# sensori_di_linea_soccer_2018.net
KiCad netlist of a schematic drawn in EAGLE
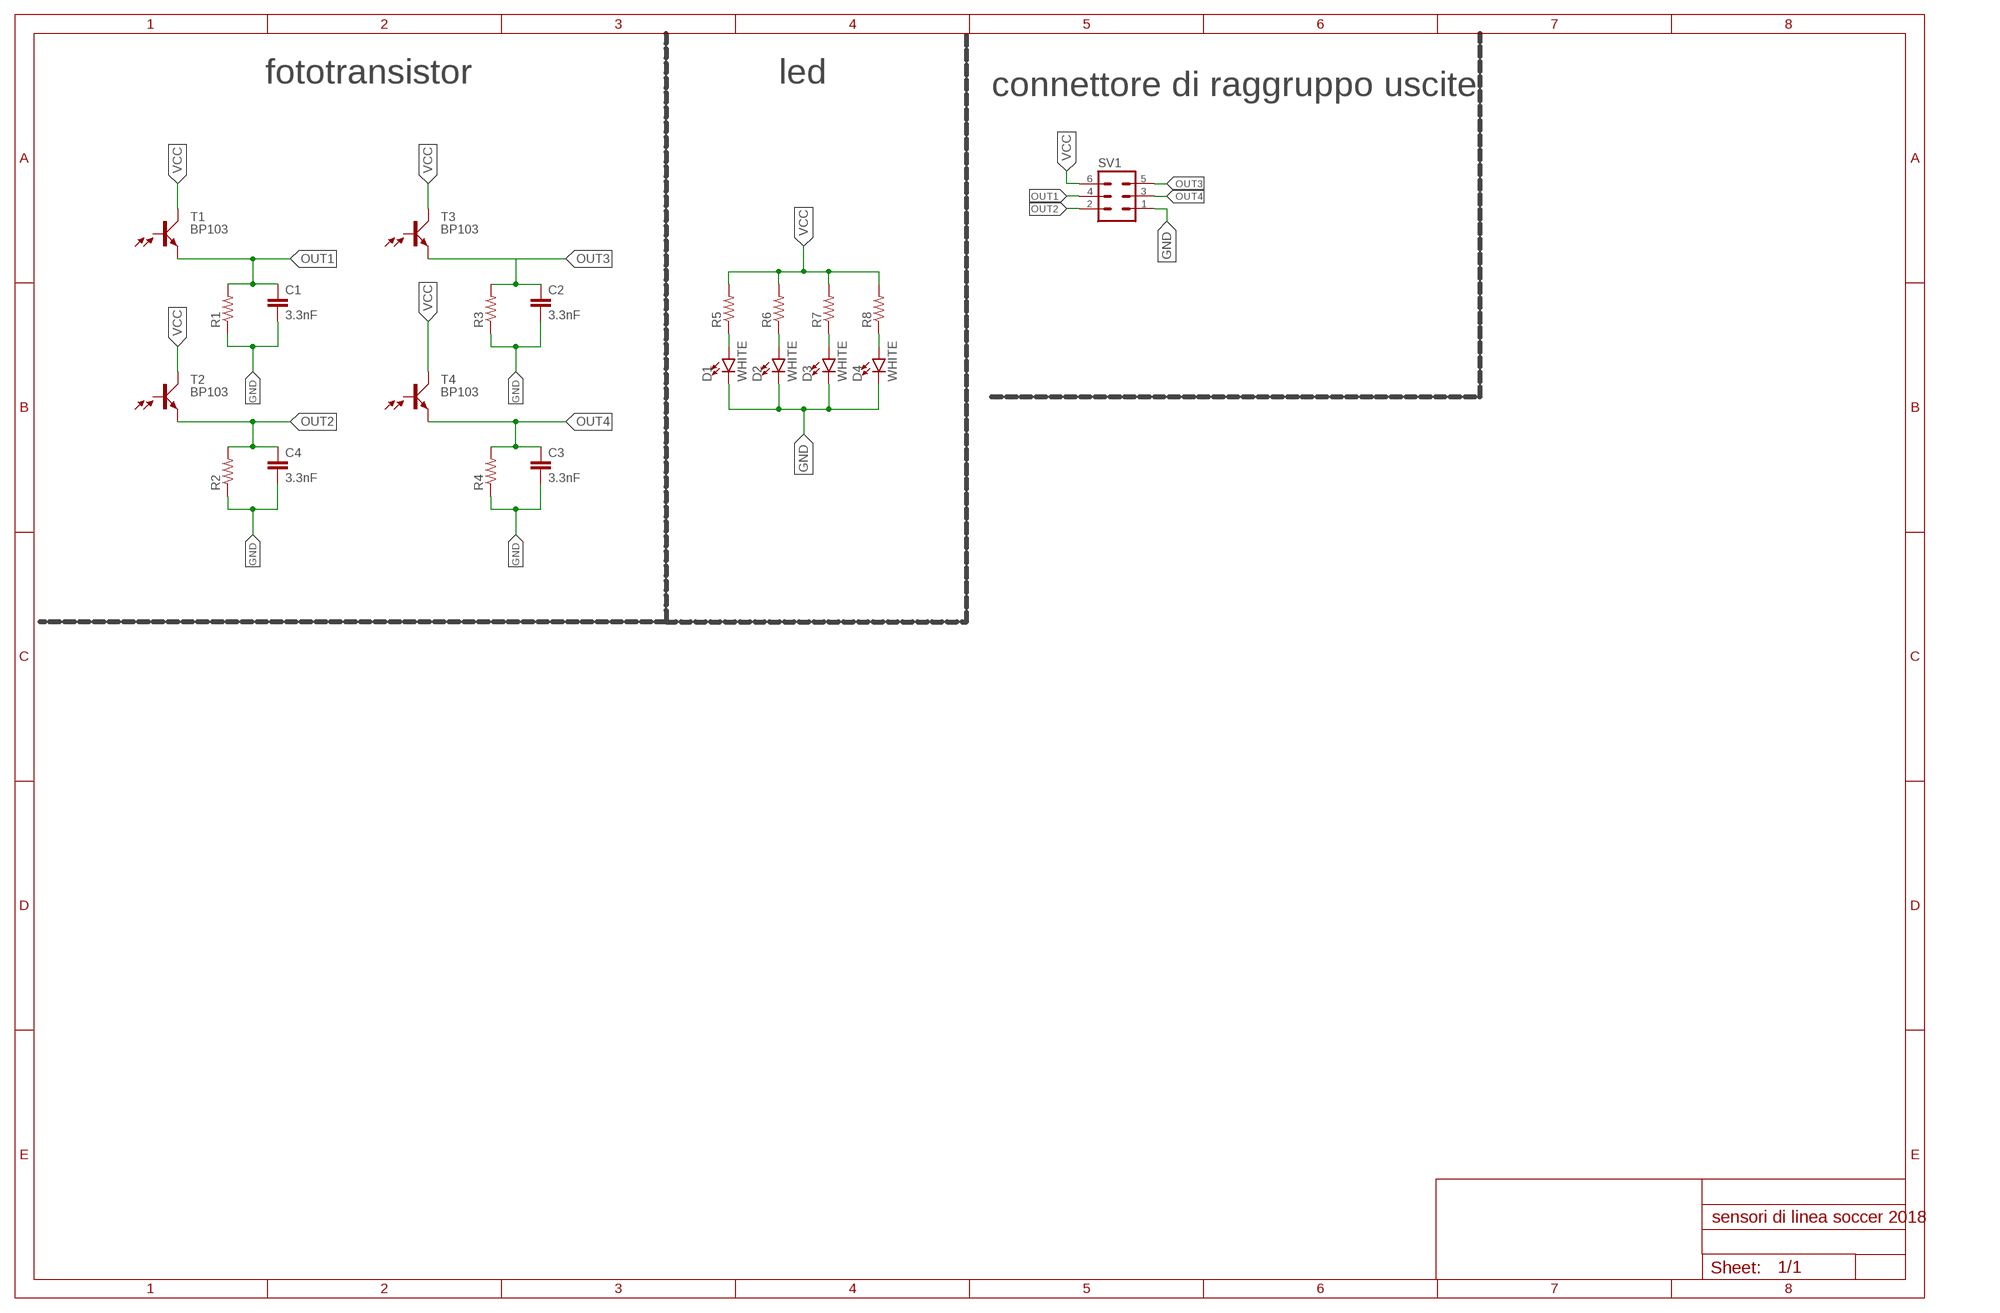
[diagram p0: schematic, sheet 1]

(export (version "E")
  (design (tool "Eeschema 10.0.6"))
  (components
    (comp (ref "C1")
      (value "3.3nF")
      (footprint "eagle-import:0603")
      (libsource (lib "eagle-import") (part "3.3NF-0603-100V-10%"))
    )
    (comp (ref "C2")
      (value "3.3nF")
      (footprint "eagle-import:0603")
      (libsource (lib "eagle-import") (part "3.3NF-0603-100V-10%"))
    )
    (comp (ref "C3")
      (value "3.3nF")
      (footprint "eagle-import:0603")
      (libsource (lib "eagle-import") (part "3.3NF-0603-100V-10%"))
    )
    (comp (ref "C4")
      (value "3.3nF")
      (footprint "eagle-import:0603")
      (libsource (lib "eagle-import") (part "3.3NF-0603-100V-10%"))
    )
    (comp (ref "D1")
      (value "WHITE")
      (footprint "eagle-import:LED-1206")
      (libsource (lib "eagle-import") (part "LED-WHITE1206"))
    )
    (comp (ref "D2")
      (value "WHITE")
      (footprint "eagle-import:LED-1206")
      (libsource (lib "eagle-import") (part "LED-WHITE1206"))
    )
    (comp (ref "D3")
      (value "WHITE")
      (footprint "eagle-import:LED-1206")
      (libsource (lib "eagle-import") (part "LED-WHITE1206"))
    )
    (comp (ref "D4")
      (value "WHITE")
      (footprint "eagle-import:LED-1206")
      (libsource (lib "eagle-import") (part "LED-WHITE1206"))
    )
    (comp (ref "R1")
      (value "R-US_0204/7")
      (footprint "eagle-import:0204_7")
      (libsource (lib "eagle-import") (part "resistor_348_R-US_0204/7"))
    )
    (comp (ref "R2")
      (value "R-US_0204/7")
      (footprint "eagle-import:0204_7")
      (libsource (lib "eagle-import") (part "resistor_348_R-US_0204/7"))
    )
    (comp (ref "R3")
      (value "R-US_0204/7")
      (footprint "eagle-import:0204_7")
      (libsource (lib "eagle-import") (part "resistor_348_R-US_0204/7"))
    )
    (comp (ref "R4")
      (value "R-US_0204/7")
      (footprint "eagle-import:0204_7")
      (libsource (lib "eagle-import") (part "resistor_348_R-US_0204/7"))
    )
    (comp (ref "R5")
      (value "R-US_0204/7")
      (footprint "eagle-import:0204_7")
      (libsource (lib "eagle-import") (part "R-US_0204/7"))
    )
    (comp (ref "R6")
      (value "R-US_0204/7")
      (footprint "eagle-import:0204_7")
      (libsource (lib "eagle-import") (part "R-US_0204/7"))
    )
    (comp (ref "R7")
      (value "R-US_0204/7")
      (footprint "eagle-import:0204_7")
      (libsource (lib "eagle-import") (part "R-US_0204/7"))
    )
    (comp (ref "R8")
      (value "R-US_0204/7")
      (footprint "eagle-import:0204_7")
      (libsource (lib "eagle-import") (part "R-US_0204/7"))
    )
    (comp (ref "SV1")
      (value "MA03-2")
      (footprint "eagle-import:MA03-2")
      (libsource (lib "eagle-import") (part "MA03-2"))
    )
    (comp (ref "T1")
      (value "BP103")
      (footprint "eagle-import:BP103")
      (libsource (lib "eagle-import") (part "BP103"))
    )
    (comp (ref "T2")
      (value "BP103")
      (footprint "eagle-import:BP103")
      (libsource (lib "eagle-import") (part "BP103"))
    )
    (comp (ref "T3")
      (value "BP103")
      (footprint "eagle-import:BP103")
      (libsource (lib "eagle-import") (part "BP103"))
    )
    (comp (ref "T4")
      (value "BP103")
      (footprint "eagle-import:BP103")
      (libsource (lib "eagle-import") (part "BP103"))
    )
  )
  (nets
    (net (code "1") (name "GND") (class "Default")
      (node (ref "C1") (pin "2") (pinfunction "2_2") (pintype "passive"))
      (node (ref "C2") (pin "2") (pinfunction "2_2") (pintype "passive"))
      (node (ref "C3") (pin "2") (pinfunction "2_2") (pintype "passive"))
      (node (ref "C4") (pin "2") (pinfunction "2_2") (pintype "passive"))
      (node (ref "D1") (pin "C") (pinfunction "C_C") (pintype "passive"))
      (node (ref "D2") (pin "C") (pinfunction "C_C") (pintype "passive"))
      (node (ref "D3") (pin "C") (pinfunction "C_C") (pintype "passive"))
      (node (ref "D4") (pin "C") (pinfunction "C_C") (pintype "passive"))
      (node (ref "R1") (pin "1") (pinfunction "1_1") (pintype "passive"))
      (node (ref "R2") (pin "1") (pinfunction "1_1") (pintype "passive"))
      (node (ref "R3") (pin "1") (pinfunction "1_1") (pintype "passive"))
      (node (ref "R4") (pin "1") (pinfunction "1_1") (pintype "passive"))
      (node (ref "SV1") (pin "1") (pinfunction "1_1") (pintype "passive"))
    )
    (net (code "2") (name "Net-(D1-PadA)") (class "Default")
      (node (ref "D1") (pin "A") (pinfunction "A_A") (pintype "passive"))
      (node (ref "R5") (pin "1") (pinfunction "1_1") (pintype "passive"))
    )
    (net (code "3") (name "Net-(D2-PadA)") (class "Default")
      (node (ref "D2") (pin "A") (pinfunction "A_A") (pintype "passive"))
      (node (ref "R6") (pin "1") (pinfunction "1_1") (pintype "passive"))
    )
    (net (code "4") (name "Net-(D3-PadA)") (class "Default")
      (node (ref "D3") (pin "A") (pinfunction "A_A") (pintype "passive"))
      (node (ref "R7") (pin "1") (pinfunction "1_1") (pintype "passive"))
    )
    (net (code "5") (name "Net-(D4-PadA)") (class "Default")
      (node (ref "D4") (pin "A") (pinfunction "A_A") (pintype "passive"))
      (node (ref "R8") (pin "1") (pinfunction "1_1") (pintype "passive"))
    )
    (net (code "6") (name "OUT1") (class "Default")
      (node (ref "C1") (pin "1") (pinfunction "1_1") (pintype "passive"))
      (node (ref "R1") (pin "2") (pinfunction "2_2") (pintype "passive"))
      (node (ref "SV1") (pin "4") (pinfunction "4_4") (pintype "passive"))
      (node (ref "T1") (pin "E") (pinfunction "E_E") (pintype "passive"))
    )
    (net (code "7") (name "OUT2") (class "Default")
      (node (ref "C4") (pin "1") (pinfunction "1_1") (pintype "passive"))
      (node (ref "R2") (pin "2") (pinfunction "2_2") (pintype "passive"))
      (node (ref "SV1") (pin "2") (pinfunction "2_2") (pintype "passive"))
      (node (ref "T2") (pin "E") (pinfunction "E_E") (pintype "passive"))
    )
    (net (code "8") (name "OUT3") (class "Default")
      (node (ref "C2") (pin "1") (pinfunction "1_1") (pintype "passive"))
      (node (ref "R3") (pin "2") (pinfunction "2_2") (pintype "passive"))
      (node (ref "SV1") (pin "5") (pinfunction "5_5") (pintype "passive"))
      (node (ref "T3") (pin "E") (pinfunction "E_E") (pintype "passive"))
    )
    (net (code "9") (name "OUT4") (class "Default")
      (node (ref "C3") (pin "1") (pinfunction "1_1") (pintype "passive"))
      (node (ref "R4") (pin "2") (pinfunction "2_2") (pintype "passive"))
      (node (ref "SV1") (pin "3") (pinfunction "3_3") (pintype "passive"))
      (node (ref "T4") (pin "E") (pinfunction "E_E") (pintype "passive"))
    )
    (net (code "10") (name "VCC") (class "Default")
      (node (ref "R5") (pin "2") (pinfunction "2_2") (pintype "passive"))
      (node (ref "R6") (pin "2") (pinfunction "2_2") (pintype "passive"))
      (node (ref "R7") (pin "2") (pinfunction "2_2") (pintype "passive"))
      (node (ref "R8") (pin "2") (pinfunction "2_2") (pintype "passive"))
      (node (ref "SV1") (pin "6") (pinfunction "6_6") (pintype "passive"))
      (node (ref "T1") (pin "C") (pinfunction "C_C") (pintype "passive"))
      (node (ref "T2") (pin "C") (pinfunction "C_C") (pintype "passive"))
      (node (ref "T3") (pin "C") (pinfunction "C_C") (pintype "passive"))
      (node (ref "T4") (pin "C") (pinfunction "C_C") (pintype "passive"))
    )
    (net (code "11") (name "unconnected-(T1-PadB)") (class "Default")
      (node (ref "T1") (pin "B") (pinfunction "B_B") (pintype "passive"))
    )
    (net (code "12") (name "unconnected-(T2-PadB)") (class "Default")
      (node (ref "T2") (pin "B") (pinfunction "B_B") (pintype "passive"))
    )
    (net (code "13") (name "unconnected-(T3-PadB)") (class "Default")
      (node (ref "T3") (pin "B") (pinfunction "B_B") (pintype "passive"))
    )
    (net (code "14") (name "unconnected-(T4-PadB)") (class "Default")
      (node (ref "T4") (pin "B") (pinfunction "B_B") (pintype "passive"))
    )
  )
)
